# Sheet1.net
KiCad netlist of a schematic drawn in Altium Designer
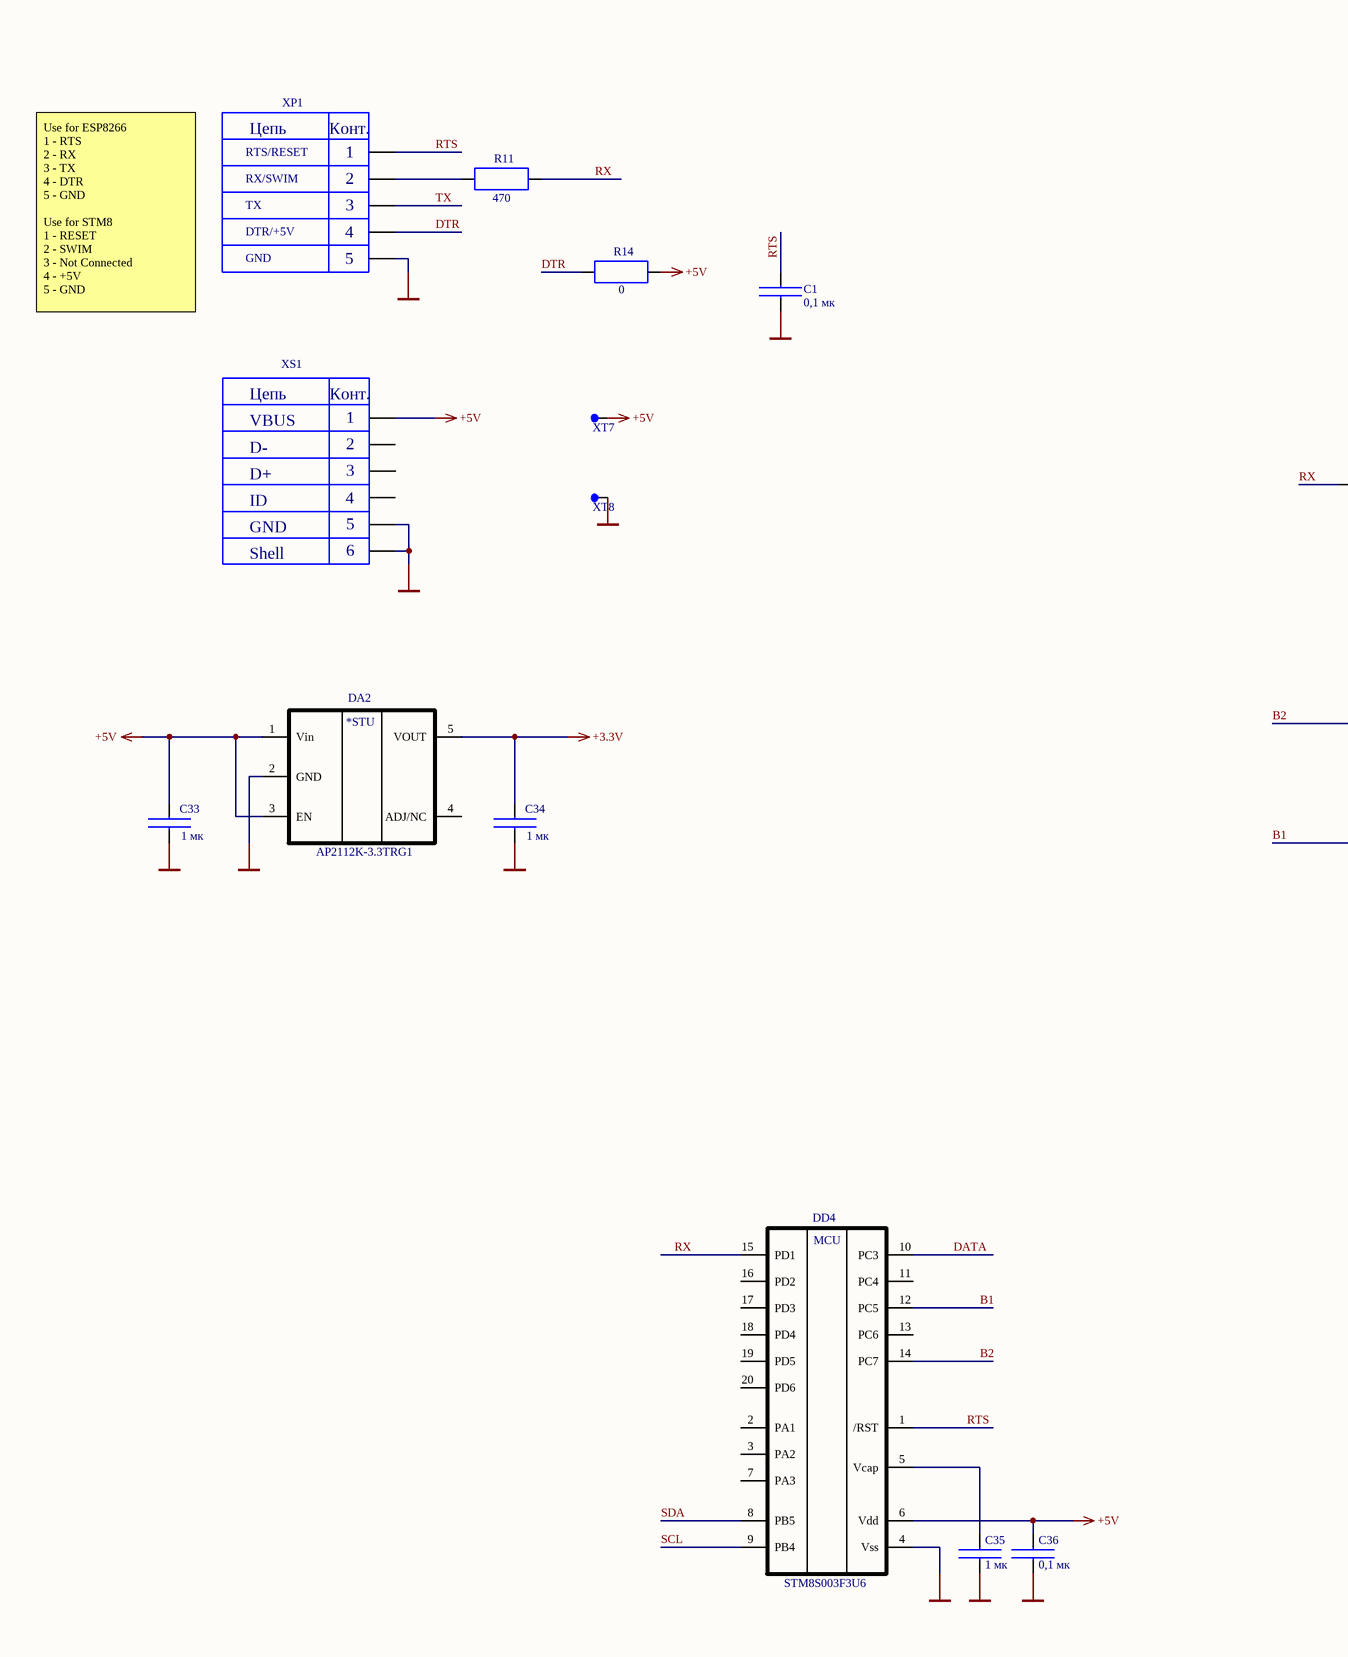
[diagram p0: Sheet1.SchDoc, left]
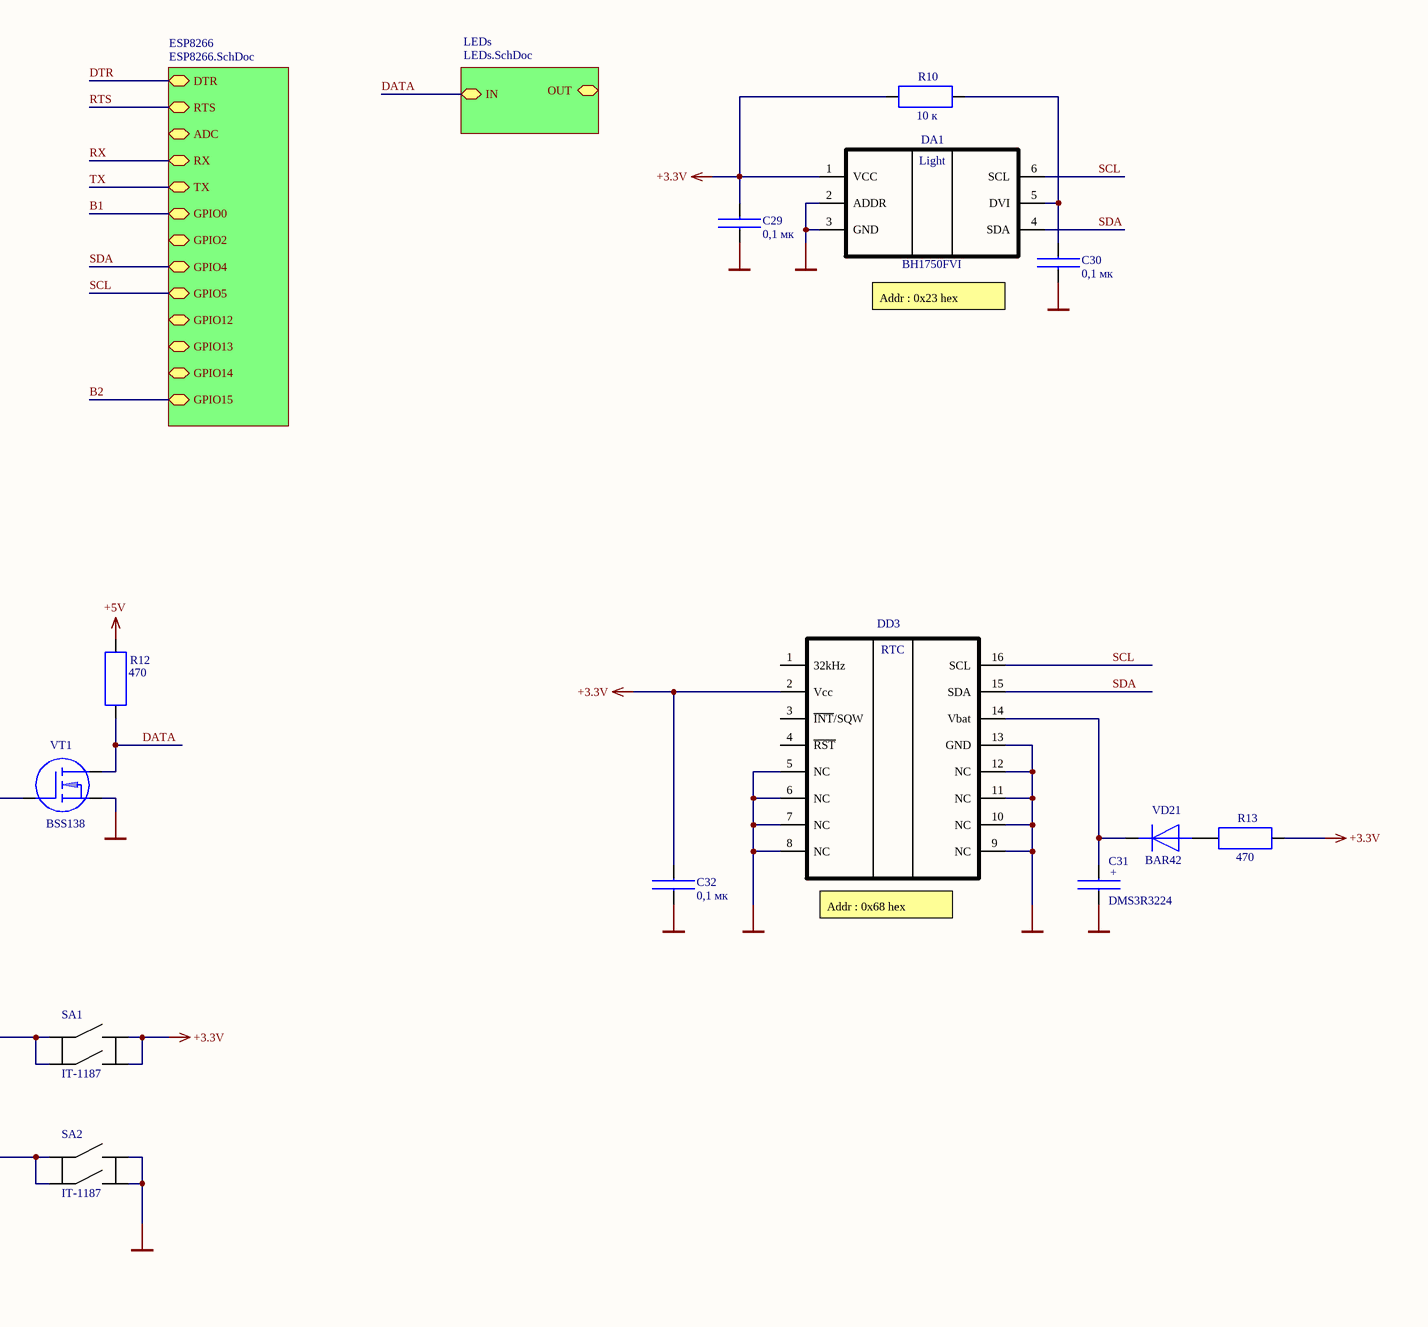
[diagram p1: Sheet1.SchDoc, right]

(export (version "E")
  (design (tool "Eeschema 10.0.6"))
  (components
    (comp (ref "C1")
      (value "0,1 мк")
      (footprint "CC1608(0603)x09")
      (description "Ceramic Chip-capacitor 0603")
      (fields (field (name "VOLTAGE") "25 / 16"))
      (libsource (lib "PCB_Project1_6") (part "CC0603 X7R uF0.22 V25/16"))
    )
    (comp (ref "C29")
      (value "0,1 мк")
      (footprint "CC1608(0603)x09")
      (description "Ceramic Chip-capacitor 0603")
      (fields (field (name "VOLTAGE") "25 / 16"))
      (libsource (lib "PCB_Project1_6") (part "CC0603 X7R uF0.22 V25/16"))
    )
    (comp (ref "C30")
      (value "0,1 мк")
      (footprint "CC1608(0603)x09")
      (description "Ceramic Chip-capacitor 0603")
      (fields (field (name "VOLTAGE") "25 / 16"))
      (libsource (lib "PCB_Project1_6") (part "CC0603 X7R uF0.22 V25/16"))
    )
    (comp (ref "C31")
      (value "DMS3R3224")
      (footprint "DMS3R3224")
      (libsource (lib "clock2") (part "DMS3R3224"))
    )
    (comp (ref "C32")
      (value "0,1 мк")
      (footprint "CC1608(0603)x09")
      (description "Ceramic Chip-capacitor 0603")
      (fields (field (name "VOLTAGE") "25 / 16"))
      (libsource (lib "PCB_Project1_6") (part "CC0603 X7R uF0.22 V25/16"))
    )
    (comp (ref "C33")
      (value "1 мк")
      (footprint "CC1608(0603)x09")
      (description "Ceramic Chip-capacitor 0603")
      (fields (field (name "VOLTAGE") "25 / 16"))
      (libsource (lib "PCB_Project1_6") (part "CC0603 X7R uF0.22 V25/16"))
    )
    (comp (ref "C34")
      (value "1 мк")
      (footprint "CC1608(0603)x09")
      (description "Ceramic Chip-capacitor 0603")
      (fields (field (name "VOLTAGE") "25 / 16"))
      (libsource (lib "PCB_Project1_6") (part "CC0603 X7R uF0.22 V25/16"))
    )
    (comp (ref "C35")
      (value "1 мк")
      (footprint "CC1608(0603)x09")
      (description "Ceramic Chip-capacitor 0603")
      (fields (field (name "VOLTAGE") "25 / 16"))
      (libsource (lib "PCB_Project1_6") (part "CC0603 X7R uF0.22 V25/16"))
    )
    (comp (ref "C36")
      (value "0,1 мк")
      (footprint "CC1608(0603)x09")
      (description "Ceramic Chip-capacitor 0603")
      (fields (field (name "VOLTAGE") "25 / 16"))
      (libsource (lib "PCB_Project1_6") (part "CC0603 X7R uF0.22 V25/16"))
    )
    (comp (ref "DA1") (value "BH1750FVI") (footprint "WSOF6I") (libsource (lib "clock2") (part "BH1750FVI")))
    (comp (ref "DA2")
      (value "AP2112K-3.3TRG1")
      (footprint "SOT23-5")
      (libsource (lib "clock2") (part "AP2112K-3.3TRG1"))
    )
    (comp (ref "DD3")
      (value "DS3231")
      (footprint "SOIC127P1030X250-16N")
      (libsource (lib "clock2") (part "DS3231"))
    )
    (comp (ref "DD4")
      (value "STM8S003F3U6")
      (footprint "QFN50P300X300X55_HS-21N")
      (libsource (lib "clock2") (part "STM8S003F3U6"))
    )
    (comp (ref "R10")
      (value "10 к")
      (footprint "RC1608(0603)x06")
      (description "Chip Resistor 0603")
      (libsource (lib "clock2") (part "1% R0603-K15.0"))
    )
    (comp (ref "R11")
      (value "470")
      (footprint "RC1608(0603)x06")
      (description "Chip Resistor 0603")
      (libsource (lib "clock2") (part "1% R0603-K15.0"))
    )
    (comp (ref "R12")
      (value "470")
      (footprint "RC1608(0603)x06")
      (description "Chip Resistor 0603")
      (libsource (lib "clock2") (part "1% R0603-K15.0"))
    )
    (comp (ref "R13")
      (value "470")
      (footprint "RC1608(0603)x06")
      (description "Chip Resistor 0603")
      (libsource (lib "clock2") (part "1% R0603-K15.0"))
    )
    (comp (ref "R14")
      (value "0")
      (footprint "RC1608(0603)x06")
      (description "Chip Resistor 0603")
      (libsource (lib "clock2") (part "1% R0603-K15.0"))
    )
    (comp (ref "SA1")
      (value "IT-1187")
      (footprint "IT-1187")
      (description "SMD Switch")
      (libsource (lib "clock2") (part "IT-1187"))
    )
    (comp (ref "SA2")
      (value "IT-1187")
      (footprint "IT-1187")
      (description "SMD Switch")
      (libsource (lib "clock2") (part "IT-1187"))
    )
    (comp (ref "VD21") (value "BAR42") (footprint "SOT-23") (libsource (lib "clock2") (part "BAR42")))
    (comp (ref "VT1") (value "BSS138") (footprint "SOT-23") (libsource (lib "clock2") (part "BSS138")))
    (comp (ref "XP1")
      (value "header5p_2.54")
      (footprint "header5p_2.54_no3d_noSilk")
      (libsource (lib "clock2") (part "header5p_2.54"))
    )
    (comp (ref "XS1")
      (value "USB/Mc-1J")
      (footprint "USB/Mc-1J")
      (description "Connector SMD USB Micro")
      (libsource (lib "clock2") (part "USB/Mc-1J"))
    )
    (comp (ref "XT7") (value "XT3") (footprint "XT3") (libsource (lib "clock2") (part "XT3")))
    (comp (ref "XT8") (value "XT3") (footprint "XT3") (libsource (lib "clock2") (part "XT3")))
  )
  (nets
    (net (code "1") (name "+3.3V") (class "Default")
      (node (ref "C29") (pin "1") (pintype "passive"))
      (node (ref "C32") (pin "1") (pintype "passive"))
      (node (ref "C34") (pin "1") (pintype "passive"))
      (node (ref "DA1") (pin "1") (pinfunction "VCC_1") (pintype "passive"))
      (node (ref "DA2") (pin "5") (pinfunction "VOUT_5") (pintype "passive"))
      (node (ref "DD3") (pin "2") (pinfunction "Vcc_2") (pintype "passive"))
      (node (ref "R10") (pin "2") (pintype "passive"))
      (node (ref "R13") (pin "1") (pintype "passive"))
      (node (ref "SA1") (pin "3") (pintype "passive"))
      (node (ref "SA1") (pin "4") (pintype "passive"))
    )
    (net (code "2") (name "+5V") (class "Default")
      (node (ref "C33") (pin "1") (pintype "passive"))
      (node (ref "C36") (pin "1") (pintype "passive"))
      (node (ref "DA2") (pin "1") (pinfunction "Vin_1") (pintype "passive"))
      (node (ref "DA2") (pin "3") (pinfunction "EN_3") (pintype "passive"))
      (node (ref "DD4") (pin "6") (pinfunction "Vdd_6") (pintype "passive"))
      (node (ref "R12") (pin "2") (pintype "passive"))
      (node (ref "R14") (pin "1") (pintype "passive"))
      (node (ref "XS1") (pin "1") (pinfunction "1_1") (pintype "passive"))
      (node (ref "XT7") (pin "1") (pintype "passive"))
    )
    (net (code "4") (name "/B1") (class "Default")
      (node (ref "DD4") (pin "12") (pinfunction "PC5_12") (pintype "passive"))
      (node (ref "SA2") (pin "1") (pintype "passive"))
      (node (ref "SA2") (pin "2") (pintype "passive"))
    )
    (net (code "5") (name "/B2") (class "Default")
      (node (ref "DD4") (pin "14") (pinfunction "PC7_14") (pintype "passive"))
      (node (ref "SA1") (pin "1") (pintype "passive"))
      (node (ref "SA1") (pin "2") (pintype "passive"))
    )
    (net (code "6") (name "/DATA") (class "Default")
      (node (ref "DD4") (pin "10") (pinfunction "PC3_10") (pintype "passive"))
      (node (ref "R12") (pin "1") (pintype "passive"))
      (node (ref "VT1") (pin "3") (pinfunction "D_3") (pintype "passive"))
    )
    (net (code "7") (name "/DTR") (class "Default")
      (node (ref "R14") (pin "2") (pintype "passive"))
      (node (ref "XP1") (pin "4") (pinfunction "4_4") (pintype "passive"))
    )
    (net (code "13") (name "/RTS") (class "Default")
      (node (ref "C1") (pin "1") (pintype "passive"))
      (node (ref "DD4") (pin "1") (pinfunction "/RST_1") (pintype "passive"))
      (node (ref "XP1") (pin "1") (pinfunction "1_1") (pintype "passive"))
    )
    (net (code "14") (name "/RX") (class "Default")
      (node (ref "DD4") (pin "15") (pinfunction "PD1_15") (pintype "passive"))
      (node (ref "R11") (pin "1") (pintype "passive"))
      (node (ref "VT1") (pin "1") (pinfunction "G_1") (pintype "passive"))
    )
    (net (code "15") (name "/SCL") (class "Default")
      (node (ref "DA1") (pin "6") (pinfunction "SCL_6") (pintype "passive"))
      (node (ref "DD3") (pin "16") (pinfunction "SCL_16") (pintype "passive"))
      (node (ref "DD4") (pin "9") (pinfunction "PB4_9") (pintype "passive"))
    )
    (net (code "16") (name "/SDA") (class "Default")
      (node (ref "DA1") (pin "4") (pinfunction "SDA_4") (pintype "passive"))
      (node (ref "DD3") (pin "15") (pinfunction "SDA_15") (pintype "passive"))
      (node (ref "DD4") (pin "8") (pinfunction "PB5_8") (pintype "passive"))
    )
    (net (code "17") (name "/TX") (class "Default")
      (node (ref "XP1") (pin "3") (pinfunction "3_3") (pintype "passive"))
    )
    (net (code "18") (name "GND") (class "Default")
      (node (ref "C1") (pin "2") (pintype "passive"))
      (node (ref "C29") (pin "2") (pintype "passive"))
      (node (ref "C30") (pin "2") (pintype "passive"))
      (node (ref "C31") (pin "-") (pintype "passive"))
      (node (ref "C32") (pin "2") (pintype "passive"))
      (node (ref "C33") (pin "2") (pintype "passive"))
      (node (ref "C34") (pin "2") (pintype "passive"))
      (node (ref "C35") (pin "2") (pintype "passive"))
      (node (ref "C36") (pin "2") (pintype "passive"))
      (node (ref "DA1") (pin "2") (pinfunction "ADDR_2") (pintype "passive"))
      (node (ref "DA1") (pin "3") (pinfunction "GND_3") (pintype "passive"))
      (node (ref "DA2") (pin "2") (pinfunction "GND_2") (pintype "passive"))
      (node (ref "DD3") (pin "10") (pinfunction "NC_10") (pintype "passive"))
      (node (ref "DD3") (pin "11") (pinfunction "NC_11") (pintype "passive"))
      (node (ref "DD3") (pin "12") (pinfunction "NC_12") (pintype "passive"))
      (node (ref "DD3") (pin "13") (pinfunction "GND_13") (pintype "passive"))
      (node (ref "DD3") (pin "5") (pinfunction "NC_5") (pintype "passive"))
      (node (ref "DD3") (pin "6") (pinfunction "NC_6") (pintype "passive"))
      (node (ref "DD3") (pin "7") (pinfunction "NC_7") (pintype "passive"))
      (node (ref "DD3") (pin "8") (pinfunction "NC_8") (pintype "passive"))
      (node (ref "DD3") (pin "9") (pinfunction "NC_9") (pintype "passive"))
      (node (ref "DD4") (pin "4") (pinfunction "Vss_4") (pintype "passive"))
      (node (ref "SA2") (pin "3") (pintype "passive"))
      (node (ref "SA2") (pin "4") (pintype "passive"))
      (node (ref "VT1") (pin "2") (pinfunction "S_2") (pintype "passive"))
      (node (ref "XP1") (pin "5") (pinfunction "5_5") (pintype "passive"))
      (node (ref "XS1") (pin "5") (pinfunction "5_5") (pintype "passive"))
      (node (ref "XS1") (pin "SH") (pinfunction "Shell_SH") (pintype "passive"))
      (node (ref "XT8") (pin "1") (pintype "passive"))
    )
    (net (code "19") (name "Net-(DA1-DVI)") (class "Default")
      (node (ref "C30") (pin "1") (pintype "passive"))
      (node (ref "DA1") (pin "5") (pinfunction "DVI_5") (pintype "passive"))
      (node (ref "R10") (pin "1") (pintype "passive"))
    )
    (net (code "20") (name "Net-(DD3-Vbat)") (class "Default")
      (node (ref "C31") (pin "+") (pintype "passive"))
      (node (ref "DD3") (pin "14") (pinfunction "Vbat_14") (pintype "passive"))
      (node (ref "VD21") (pin "3") (pintype "passive"))
    )
    (net (code "21") (name "Net-(DD4-Vcap)") (class "Default")
      (node (ref "C35") (pin "1") (pintype "passive"))
      (node (ref "DD4") (pin "5") (pinfunction "Vcap_5") (pintype "passive"))
    )
    (net (code "22") (name "Net-(R11-Pad2)") (class "Default")
      (node (ref "R11") (pin "2") (pintype "passive"))
      (node (ref "XP1") (pin "2") (pinfunction "2_2") (pintype "passive"))
    )
    (net (code "23") (name "Net-(R13-Pad2)") (class "Default")
      (node (ref "R13") (pin "2") (pintype "passive"))
      (node (ref "VD21") (pin "1") (pintype "passive"))
    )
    (net (code "24") (name "unconnected-(DA2-ADJ{slash}NC-Pad4)") (class "Default")
      (node (ref "DA2") (pin "4") (pinfunction "ADJ/NC_4") (pintype "passive"))
    )
    (net (code "25") (name "unconnected-(DD3-32kHz-Pad1)") (class "Default")
      (node (ref "DD3") (pin "1") (pinfunction "32kHz_1") (pintype "passive"))
    )
    (net (code "26") (name "unconnected-(DD3-~{INT}{slash}SQW-Pad3)") (class "Default")
      (node (ref "DD3") (pin "3") (pinfunction "~{INT}/SQW_3") (pintype "passive"))
    )
    (net (code "27") (name "unconnected-(DD3-~{RST}-Pad4)") (class "Default")
      (node (ref "DD3") (pin "4") (pinfunction "~{RST}_4") (pintype "passive"))
    )
    (net (code "28") (name "unconnected-(DD4-PA1-Pad2)") (class "Default")
      (node (ref "DD4") (pin "2") (pinfunction "PA1_2") (pintype "passive"))
    )
    (net (code "29") (name "unconnected-(DD4-PA2-Pad3)") (class "Default")
      (node (ref "DD4") (pin "3") (pinfunction "PA2_3") (pintype "passive"))
    )
    (net (code "30") (name "unconnected-(DD4-PA3-Pad7)") (class "Default")
      (node (ref "DD4") (pin "7") (pinfunction "PA3_7") (pintype "passive"))
    )
    (net (code "31") (name "unconnected-(DD4-PC4-Pad11)") (class "Default")
      (node (ref "DD4") (pin "11") (pinfunction "PC4_11") (pintype "passive"))
    )
    (net (code "32") (name "unconnected-(DD4-PC6-Pad13)") (class "Default")
      (node (ref "DD4") (pin "13") (pinfunction "PC6_13") (pintype "passive"))
    )
    (net (code "33") (name "unconnected-(DD4-PD2-Pad16)") (class "Default")
      (node (ref "DD4") (pin "16") (pinfunction "PD2_16") (pintype "passive"))
    )
    (net (code "34") (name "unconnected-(DD4-PD3-Pad17)") (class "Default")
      (node (ref "DD4") (pin "17") (pinfunction "PD3_17") (pintype "passive"))
    )
    (net (code "35") (name "unconnected-(DD4-PD4-Pad18)") (class "Default")
      (node (ref "DD4") (pin "18") (pinfunction "PD4_18") (pintype "passive"))
    )
    (net (code "36") (name "unconnected-(DD4-PD5-Pad19)") (class "Default")
      (node (ref "DD4") (pin "19") (pinfunction "PD5_19") (pintype "passive"))
    )
    (net (code "37") (name "unconnected-(DD4-PD6-Pad20)") (class "Default")
      (node (ref "DD4") (pin "20") (pinfunction "PD6_20") (pintype "passive"))
    )
    (net (code "38") (name "unconnected-(XS1-Pad2)") (class "Default")
      (node (ref "XS1") (pin "2") (pinfunction "2_2") (pintype "passive"))
    )
    (net (code "39") (name "unconnected-(XS1-Pad3)") (class "Default")
      (node (ref "XS1") (pin "3") (pinfunction "3_3") (pintype "passive"))
    )
    (net (code "40") (name "unconnected-(XS1-Pad4)") (class "Default")
      (node (ref "XS1") (pin "4") (pinfunction "4_4") (pintype "passive"))
    )
  )
)
